# Petra.net
KiCad netlist of a schematic drawn in EAGLE
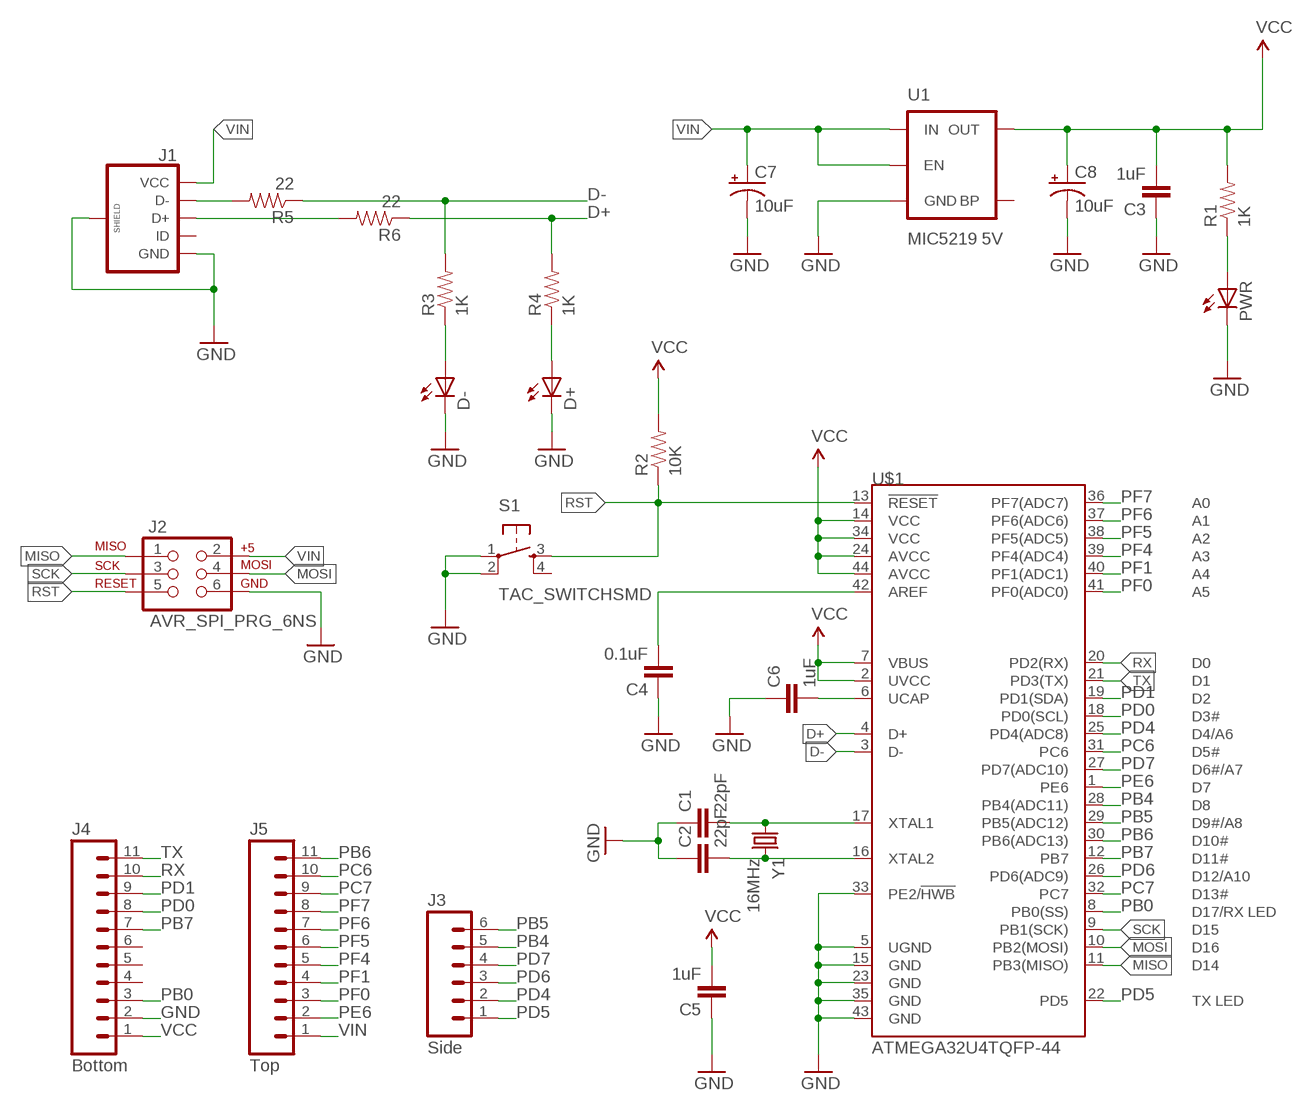
[diagram p0: schematic, sheet 1]

(export (version "E")
  (design (tool "Eeschema 10.0.6"))
  (components
    (comp (ref "C1")
      (value "22pF")
      (footprint "eagle-import:0402-CAP")
      (libsource (lib "eagle-import") (part "CAP0402-CAP"))
    )
    (comp (ref "C2")
      (value "22pF")
      (footprint "eagle-import:0402-CAP")
      (libsource (lib "eagle-import") (part "CAP0402-CAP"))
    )
    (comp (ref "C3")
      (value "1uF")
      (footprint "eagle-import:0402-CAP")
      (libsource (lib "eagle-import") (part "CAP0402-CAP"))
    )
    (comp (ref "C4")
      (value "0.1uF")
      (footprint "eagle-import:0402-CAP")
      (libsource (lib "eagle-import") (part "CAP0402-CAP"))
    )
    (comp (ref "C5")
      (value "1uF")
      (footprint "eagle-import:0402-CAP")
      (libsource (lib "eagle-import") (part "CAP0402-CAP"))
    )
    (comp (ref "C6")
      (value "1uF")
      (footprint "eagle-import:0402-CAP")
      (libsource (lib "eagle-import") (part "CAP0402-CAP"))
    )
    (comp (ref "C7")
      (value "10uF")
      (footprint "eagle-import:EIA3216")
      (libsource (lib "eagle-import") (part "CAP_POL1206"))
    )
    (comp (ref "C8")
      (value "10uF")
      (footprint "eagle-import:EIA3216")
      (libsource (lib "eagle-import") (part "CAP_POL1206"))
    )
    (comp (ref "D+")
      (value "LEDCHIP-LED0805")
      (footprint "eagle-import:CHIP-LED0805")
      (libsource (lib "eagle-import") (part "LEDCHIP-LED0805"))
    )
    (comp (ref "D-")
      (value "LEDCHIP-LED0805")
      (footprint "eagle-import:CHIP-LED0805")
      (libsource (lib "eagle-import") (part "LEDCHIP-LED0805"))
    )
    (comp (ref "J1")
      (value "USB_MICROB_PLUGCONN-11752")
      (footprint "eagle-import:USB-B-MICRO-SMD_V03")
      (libsource (lib "eagle-import") (part "USB_MICROB_PLUGCONN-11752"))
    )
    (comp (ref "J2")
      (value "AVR_SPI_PRG_6NS")
      (footprint "eagle-import:2X3-NS")
      (libsource (lib "eagle-import") (part "AVR_SPI_PRG_6NS"))
    )
    (comp (ref "J3")
      (value "Side")
      (footprint "eagle-import:1X06")
      (libsource (lib "eagle-import") (part "HEADER_1X06"))
    )
    (comp (ref "J4")
      (value "Bottom")
      (footprint "eagle-import:1X11")
      (libsource (lib "eagle-import") (part "HEADER_1X11"))
    )
    (comp (ref "J5")
      (value "Top")
      (footprint "eagle-import:1X11")
      (libsource (lib "eagle-import") (part "HEADER_1X11"))
    )
    (comp (ref "PWR")
      (value "LEDCHIP-LED0805")
      (footprint "eagle-import:CHIP-LED0805")
      (libsource (lib "eagle-import") (part "LEDCHIP-LED0805"))
    )
    (comp (ref "R1")
      (value "1K")
      (footprint "eagle-import:0603-RES")
      (libsource (lib "eagle-import") (part "10KOHM-1/10W-1%(0603)0603"))
    )
    (comp (ref "R2")
      (value "10K")
      (footprint "eagle-import:0603-RES")
      (libsource (lib "eagle-import") (part "10KOHM-1/10W-1%(0603)0603"))
    )
    (comp (ref "R3")
      (value "1K")
      (footprint "eagle-import:0603-RES")
      (libsource (lib "eagle-import") (part "10KOHM-1/10W-1%(0603)0603"))
    )
    (comp (ref "R4")
      (value "1K")
      (footprint "eagle-import:0603-RES")
      (libsource (lib "eagle-import") (part "10KOHM-1/10W-1%(0603)0603"))
    )
    (comp (ref "R5")
      (value "22")
      (footprint "eagle-import:0603-RES")
      (libsource (lib "eagle-import") (part "10KOHM-1/10W-1%(0603)0603"))
    )
    (comp (ref "R6")
      (value "22")
      (footprint "eagle-import:0603-RES")
      (libsource (lib "eagle-import") (part "10KOHM-1/10W-1%(0603)0603"))
    )
    (comp (ref "S1")
      (value "TAC_SWITCHSMD")
      (footprint "eagle-import:TACTILE-SWITCH-SMD")
      (libsource (lib "eagle-import") (part "TAC_SWITCHSMD"))
    )
    (comp (ref "U$1")
      (value "ATMEGA32U4TQFP-44")
      (footprint "eagle-import:TQFP44")
      (libsource (lib "eagle-import") (part "ATMEGA32U4TQFP-44"))
    )
    (comp (ref "U1")
      (value "MIC5219 5V")
      (footprint "eagle-import:SOT23-5")
      (libsource (lib "eagle-import") (part "V_REG_MIC52195V"))
    )
    (comp (ref "Y1")
      (value "16MHz")
      (footprint "eagle-import:CRYSTAL-SMD-5X3")
      (libsource (lib "eagle-import") (part "CRYSTALCRYSTAL-SMD-5X3-16MHZ"))
    )
  )
  (nets
    (net (code "1") (name "/PB0") (class "Default")
      (node (ref "J4") (pin "3") (pinfunction "3_3") (pintype "passive"))
      (node (ref "U$1") (pin "8") (pinfunction "PB0(SS)_8") (pintype "bidirectional"))
    )
    (net (code "2") (name "/PB4") (class "Default")
      (node (ref "J3") (pin "5") (pinfunction "5_5") (pintype "passive"))
      (node (ref "U$1") (pin "28") (pinfunction "PB4(ADC11)_28") (pintype "bidirectional"))
    )
    (net (code "3") (name "/PB5") (class "Default")
      (node (ref "J3") (pin "6") (pinfunction "6_6") (pintype "passive"))
      (node (ref "U$1") (pin "29") (pinfunction "PB5(ADC12)_29") (pintype "bidirectional"))
    )
    (net (code "4") (name "/PB6") (class "Default")
      (node (ref "J5") (pin "11") (pinfunction "11_11") (pintype "passive"))
      (node (ref "U$1") (pin "30") (pinfunction "PB6(ADC13)_30") (pintype "bidirectional"))
    )
    (net (code "5") (name "/PB7") (class "Default")
      (node (ref "J4") (pin "7") (pinfunction "7_7") (pintype "passive"))
      (node (ref "U$1") (pin "12") (pinfunction "PB7_12") (pintype "bidirectional"))
    )
    (net (code "6") (name "/PC6") (class "Default")
      (node (ref "J5") (pin "10") (pinfunction "10_10") (pintype "passive"))
      (node (ref "U$1") (pin "31") (pinfunction "PC6_31") (pintype "bidirectional"))
    )
    (net (code "7") (name "/PC7") (class "Default")
      (node (ref "J5") (pin "9") (pinfunction "9_9") (pintype "passive"))
      (node (ref "U$1") (pin "32") (pinfunction "PC7_32") (pintype "bidirectional"))
    )
    (net (code "8") (name "/PD0") (class "Default")
      (node (ref "J4") (pin "8") (pinfunction "8_8") (pintype "passive"))
      (node (ref "U$1") (pin "18") (pinfunction "PD0(SCL)_18") (pintype "bidirectional"))
    )
    (net (code "9") (name "/PD1") (class "Default")
      (node (ref "J4") (pin "9") (pinfunction "9_9") (pintype "passive"))
      (node (ref "U$1") (pin "19") (pinfunction "PD1(SDA)_19") (pintype "bidirectional"))
    )
    (net (code "10") (name "/PD4") (class "Default")
      (node (ref "J3") (pin "2") (pinfunction "2_2") (pintype "passive"))
      (node (ref "U$1") (pin "25") (pinfunction "PD4(ADC8)_25") (pintype "bidirectional"))
    )
    (net (code "11") (name "/PD5") (class "Default")
      (node (ref "J3") (pin "1") (pinfunction "1_1") (pintype "passive"))
      (node (ref "U$1") (pin "22") (pinfunction "PD5_22") (pintype "bidirectional"))
    )
    (net (code "12") (name "/PD6") (class "Default")
      (node (ref "J3") (pin "3") (pinfunction "3_3") (pintype "passive"))
      (node (ref "U$1") (pin "26") (pinfunction "PD6(ADC9)_26") (pintype "bidirectional"))
    )
    (net (code "13") (name "/PD7") (class "Default")
      (node (ref "J3") (pin "4") (pinfunction "4_4") (pintype "passive"))
      (node (ref "U$1") (pin "27") (pinfunction "PD7(ADC10)_27") (pintype "bidirectional"))
    )
    (net (code "14") (name "/PE6") (class "Default")
      (node (ref "J5") (pin "2") (pinfunction "2_2") (pintype "passive"))
      (node (ref "U$1") (pin "1") (pinfunction "PE6_1") (pintype "bidirectional"))
    )
    (net (code "15") (name "/PF0") (class "Default")
      (node (ref "J5") (pin "3") (pinfunction "3_3") (pintype "passive"))
      (node (ref "U$1") (pin "41") (pinfunction "PF0(ADC0)_41") (pintype "bidirectional"))
    )
    (net (code "16") (name "/PF1") (class "Default")
      (node (ref "J5") (pin "4") (pinfunction "4_4") (pintype "passive"))
      (node (ref "U$1") (pin "40") (pinfunction "PF1(ADC1)_40") (pintype "bidirectional"))
    )
    (net (code "17") (name "/PF4") (class "Default")
      (node (ref "J5") (pin "5") (pinfunction "5_5") (pintype "passive"))
      (node (ref "U$1") (pin "39") (pinfunction "PF4(ADC4)_39") (pintype "bidirectional"))
    )
    (net (code "18") (name "/PF5") (class "Default")
      (node (ref "J5") (pin "6") (pinfunction "6_6") (pintype "passive"))
      (node (ref "U$1") (pin "38") (pinfunction "PF5(ADC5)_38") (pintype "bidirectional"))
    )
    (net (code "19") (name "/PF6") (class "Default")
      (node (ref "J5") (pin "7") (pinfunction "7_7") (pintype "passive"))
      (node (ref "U$1") (pin "37") (pinfunction "PF6(ADC6)_37") (pintype "bidirectional"))
    )
    (net (code "20") (name "/PF7") (class "Default")
      (node (ref "J5") (pin "8") (pinfunction "8_8") (pintype "passive"))
      (node (ref "U$1") (pin "36") (pinfunction "PF7(ADC7)_36") (pintype "bidirectional"))
    )
    (net (code "21") (name "D+") (class "Default")
      (node (ref "R4") (pin "2") (pinfunction "2_2") (pintype "passive"))
      (node (ref "R6") (pin "1") (pinfunction "1_1") (pintype "passive"))
      (node (ref "U$1") (pin "4") (pinfunction "D+_4") (pintype "bidirectional"))
    )
    (net (code "22") (name "D-") (class "Default")
      (node (ref "R3") (pin "2") (pinfunction "2_2") (pintype "passive"))
      (node (ref "R5") (pin "1") (pinfunction "1_1") (pintype "passive"))
      (node (ref "U$1") (pin "3") (pinfunction "D-_3") (pintype "bidirectional"))
    )
    (net (code "23") (name "GND") (class "Default")
      (node (ref "C1") (pin "1") (pinfunction "1_1") (pintype "passive"))
      (node (ref "C2") (pin "1") (pinfunction "1_1") (pintype "passive"))
      (node (ref "C3") (pin "1") (pinfunction "1_1") (pintype "passive"))
      (node (ref "C4") (pin "1") (pinfunction "1_1") (pintype "passive"))
      (node (ref "C5") (pin "1") (pinfunction "1_1") (pintype "passive"))
      (node (ref "C6") (pin "1") (pinfunction "1_1") (pintype "passive"))
      (node (ref "C7") (pin "C") (pinfunction "-_C") (pintype "passive"))
      (node (ref "C8") (pin "C") (pinfunction "-_C") (pintype "passive"))
      (node (ref "D+") (pin "C") (pinfunction "C_C") (pintype "passive"))
      (node (ref "D-") (pin "C") (pinfunction "C_C") (pintype "passive"))
      (node (ref "J1") (pin "GND") (pinfunction "GND_GND") (pintype "bidirectional"))
      (node (ref "J1") (pin "SHIELD1") (pinfunction "SHIELD_SHIELD1") (pintype "bidirectional"))
      (node (ref "J1") (pin "SHIELD2") (pinfunction "SHIELD_SHIELD2") (pintype "bidirectional"))
      (node (ref "J1") (pin "SHIELD3") (pinfunction "SHIELD_SHIELD3") (pintype "bidirectional"))
      (node (ref "J2") (pin "6") (pinfunction "6_6") (pintype "passive"))
      (node (ref "J4") (pin "2") (pinfunction "2_2") (pintype "passive"))
      (node (ref "PWR") (pin "C") (pinfunction "C_C") (pintype "passive"))
      (node (ref "S1") (pin "1") (pinfunction "1_1") (pintype "passive"))
      (node (ref "S1") (pin "2") (pinfunction "2_2") (pintype "passive"))
      (node (ref "U$1") (pin "15") (pinfunction "GND_15") (pintype "bidirectional"))
      (node (ref "U$1") (pin "23") (pinfunction "GND_23") (pintype "bidirectional"))
      (node (ref "U$1") (pin "33") (pinfunction "PE2/~{HWB}_33") (pintype "bidirectional"))
      (node (ref "U$1") (pin "35") (pinfunction "GND_35") (pintype "bidirectional"))
      (node (ref "U$1") (pin "43") (pinfunction "GND_43") (pintype "bidirectional"))
      (node (ref "U$1") (pin "5") (pinfunction "UGND_5") (pintype "bidirectional"))
      (node (ref "U1") (pin "2") (pinfunction "GND_2") (pintype "input"))
    )
    (net (code "24") (name "MISO") (class "Default")
      (node (ref "J2") (pin "1") (pinfunction "1_1") (pintype "passive"))
      (node (ref "U$1") (pin "11") (pinfunction "PB3(MISO)_11") (pintype "bidirectional"))
    )
    (net (code "25") (name "MOSI") (class "Default")
      (node (ref "J2") (pin "4") (pinfunction "4_4") (pintype "passive"))
      (node (ref "U$1") (pin "10") (pinfunction "PB2(MOSI)_10") (pintype "bidirectional"))
    )
    (net (code "26") (name "Net-(D+-PadA)") (class "Default")
      (node (ref "D+") (pin "A") (pinfunction "A_A") (pintype "passive"))
      (node (ref "R4") (pin "1") (pinfunction "1_1") (pintype "passive"))
    )
    (net (code "27") (name "Net-(D--PadA)") (class "Default")
      (node (ref "D-") (pin "A") (pinfunction "A_A") (pintype "passive"))
      (node (ref "R3") (pin "1") (pinfunction "1_1") (pintype "passive"))
    )
    (net (code "28") (name "Net-(J1-PadD+)") (class "Default")
      (node (ref "J1") (pin "D+") (pinfunction "D+_D+") (pintype "bidirectional"))
      (node (ref "R6") (pin "2") (pinfunction "2_2") (pintype "passive"))
    )
    (net (code "29") (name "Net-(J1-PadD-)") (class "Default")
      (node (ref "J1") (pin "D-") (pinfunction "D-_D-") (pintype "bidirectional"))
      (node (ref "R5") (pin "2") (pinfunction "2_2") (pintype "passive"))
    )
    (net (code "30") (name "Net-(PWR-PadA)") (class "Default")
      (node (ref "PWR") (pin "A") (pinfunction "A_A") (pintype "passive"))
      (node (ref "R1") (pin "1") (pinfunction "1_1") (pintype "passive"))
    )
    (net (code "31") (name "Net-(U$1-AREF)") (class "Default")
      (node (ref "C4") (pin "2") (pinfunction "2_2") (pintype "passive"))
      (node (ref "U$1") (pin "42") (pinfunction "AREF_42") (pintype "bidirectional"))
    )
    (net (code "32") (name "Net-(U$1-UCAP)") (class "Default")
      (node (ref "C6") (pin "2") (pinfunction "2_2") (pintype "passive"))
      (node (ref "U$1") (pin "6") (pinfunction "UCAP_6") (pintype "bidirectional"))
    )
    (net (code "33") (name "Net-(U$1-XTAL1)") (class "Default")
      (node (ref "C1") (pin "2") (pinfunction "2_2") (pintype "passive"))
      (node (ref "U$1") (pin "17") (pinfunction "XTAL1_17") (pintype "bidirectional"))
      (node (ref "Y1") (pin "1") (pinfunction "1_1") (pintype "passive"))
    )
    (net (code "34") (name "Net-(U$1-XTAL2)") (class "Default")
      (node (ref "C2") (pin "2") (pinfunction "2_2") (pintype "passive"))
      (node (ref "U$1") (pin "16") (pinfunction "XTAL2_16") (pintype "bidirectional"))
      (node (ref "Y1") (pin "3") (pinfunction "2_3") (pintype "passive"))
    )
    (net (code "35") (name "RST") (class "Default")
      (node (ref "J2") (pin "5") (pinfunction "5_5") (pintype "passive"))
      (node (ref "R2") (pin "1") (pinfunction "1_1") (pintype "passive"))
      (node (ref "S1") (pin "3") (pinfunction "3_3") (pintype "passive"))
      (node (ref "U$1") (pin "13") (pinfunction "~{RESET}_13") (pintype "bidirectional"))
    )
    (net (code "36") (name "RX") (class "Default")
      (node (ref "J4") (pin "10") (pinfunction "10_10") (pintype "passive"))
      (node (ref "U$1") (pin "20") (pinfunction "PD2(RX)_20") (pintype "bidirectional"))
    )
    (net (code "37") (name "SCK") (class "Default")
      (node (ref "J2") (pin "3") (pinfunction "3_3") (pintype "passive"))
      (node (ref "U$1") (pin "9") (pinfunction "PB1(SCK)_9") (pintype "bidirectional"))
    )
    (net (code "38") (name "TX") (class "Default")
      (node (ref "J4") (pin "11") (pinfunction "11_11") (pintype "passive"))
      (node (ref "U$1") (pin "21") (pinfunction "PD3(TX)_21") (pintype "bidirectional"))
    )
    (net (code "39") (name "VCC") (class "Default")
      (node (ref "C3") (pin "2") (pinfunction "2_2") (pintype "passive"))
      (node (ref "C5") (pin "2") (pinfunction "2_2") (pintype "passive"))
      (node (ref "C8") (pin "A") (pinfunction "+_A") (pintype "passive"))
      (node (ref "J4") (pin "1") (pinfunction "1_1") (pintype "passive"))
      (node (ref "R1") (pin "2") (pinfunction "2_2") (pintype "passive"))
      (node (ref "R2") (pin "2") (pinfunction "2_2") (pintype "passive"))
      (node (ref "U$1") (pin "14") (pinfunction "VCC_14") (pintype "bidirectional"))
      (node (ref "U$1") (pin "2") (pinfunction "UVCC_2") (pintype "bidirectional"))
      (node (ref "U$1") (pin "24") (pinfunction "AVCC_24") (pintype "bidirectional"))
      (node (ref "U$1") (pin "34") (pinfunction "VCC_34") (pintype "bidirectional"))
      (node (ref "U$1") (pin "44") (pinfunction "AVCC_44") (pintype "bidirectional"))
      (node (ref "U$1") (pin "7") (pinfunction "VBUS_7") (pintype "bidirectional"))
      (node (ref "U1") (pin "5") (pinfunction "OUT_5") (pintype "passive"))
    )
    (net (code "40") (name "VIN") (class "Default")
      (node (ref "C7") (pin "A") (pinfunction "+_A") (pintype "passive"))
      (node (ref "J1") (pin "VBUS") (pinfunction "VCC_VBUS") (pintype "bidirectional"))
      (node (ref "J2") (pin "2") (pinfunction "2_2") (pintype "passive"))
      (node (ref "J5") (pin "1") (pinfunction "1_1") (pintype "passive"))
      (node (ref "U1") (pin "1") (pinfunction "IN_1") (pintype "input"))
      (node (ref "U1") (pin "3") (pinfunction "EN_3") (pintype "input"))
    )
    (net (code "41") (name "unconnected-(J1-PadID)") (class "Default")
      (node (ref "J1") (pin "ID") (pinfunction "ID_ID") (pintype "bidirectional"))
    )
    (net (code "42") (name "unconnected-(J4-Pad4)") (class "Default")
      (node (ref "J4") (pin "4") (pinfunction "4_4") (pintype "passive"))
    )
    (net (code "43") (name "unconnected-(J4-Pad5)") (class "Default")
      (node (ref "J4") (pin "5") (pinfunction "5_5") (pintype "passive"))
    )
    (net (code "44") (name "unconnected-(J4-Pad6)") (class "Default")
      (node (ref "J4") (pin "6") (pinfunction "6_6") (pintype "passive"))
    )
    (net (code "45") (name "unconnected-(S1-Pad4)") (class "Default")
      (node (ref "S1") (pin "4") (pinfunction "4_4") (pintype "passive"))
    )
    (net (code "46") (name "unconnected-(U1-BP-Pad4)") (class "Default")
      (node (ref "U1") (pin "4") (pinfunction "BP_4") (pintype "input"))
    )
  )
)
